# 401_GridPos4.net
KiCad netlist of a schematic drawn in Altium Designer
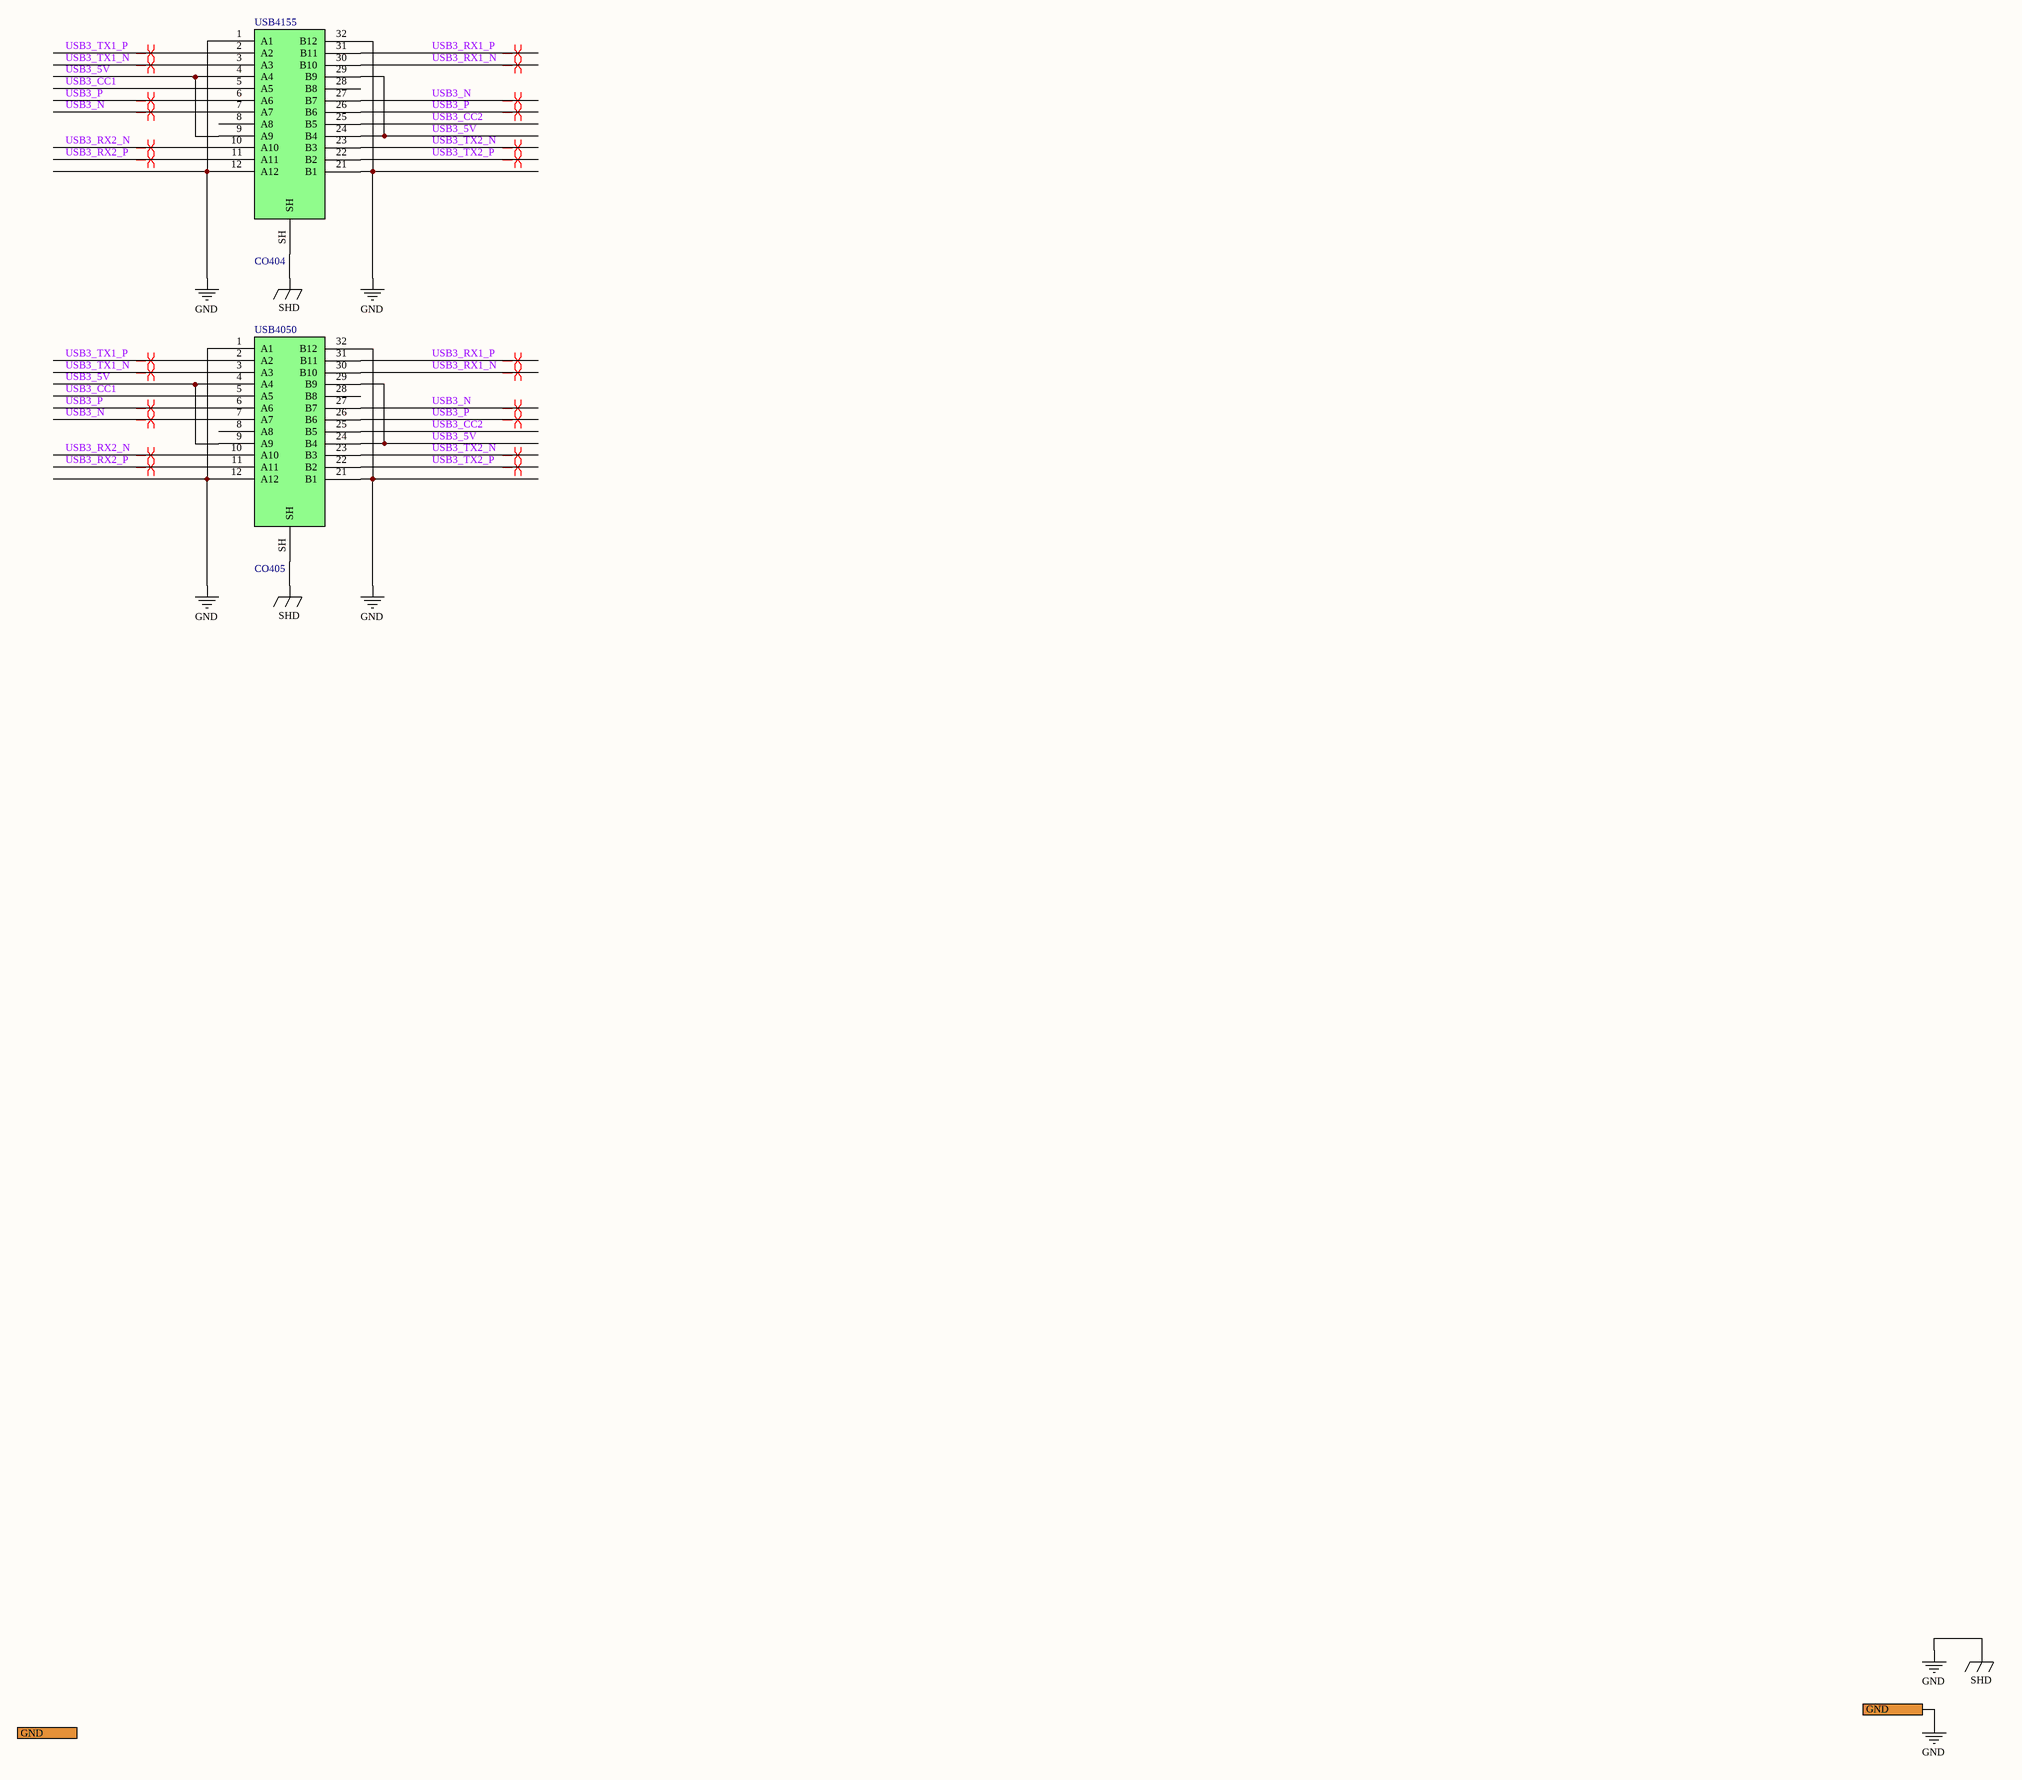
[diagram p0: 401_GridPos4.SchDoc]

(export (version "E")
  (design (tool "Eeschema 10.0.6"))
  (components
    (comp (ref "CO404")
      (value "USB4155")
      (footprint "USB4155-03-C")
      (description "USB C connector Plug Horizontal")
      (fields
        (field (name "REFVAL") "USB4155")
        (field (name "PART NUMBER") "CO0031")
        (field (name "MANFACTPART") "USB4155-03-C")
      )
      (libsource (lib "GTS_Database") (part "USB-CC"))
    )
    (comp (ref "CO405")
      (value "USB4050")
      (footprint "USB4050-30-A")
      (description "USB C connector Receptacle Horizontal")
      (fields
        (field (name "REFVAL") "USB4050")
        (field (name "PART NUMBER") "CO0039")
        (field (name "MANFACTPART") "USB4050-30-A")
      )
      (libsource (lib "GTS_Database") (part "USB-CC"))
    )
  )
  (nets
    (net (code "1") (name "/USB3_5V") (class "Default")
      (node (ref "CO404") (pin "24") (pinfunction "B4_24") (pintype "passive"))
      (node (ref "CO404") (pin "29") (pinfunction "B9_29") (pintype "passive"))
      (node (ref "CO404") (pin "4") (pinfunction "A4_4") (pintype "passive"))
      (node (ref "CO404") (pin "9") (pinfunction "A9_9") (pintype "passive"))
      (node (ref "CO405") (pin "24") (pinfunction "B4_24") (pintype "passive"))
      (node (ref "CO405") (pin "29") (pinfunction "B9_29") (pintype "passive"))
      (node (ref "CO405") (pin "4") (pinfunction "A4_4") (pintype "passive"))
      (node (ref "CO405") (pin "9") (pinfunction "A9_9") (pintype "passive"))
    )
    (net (code "2") (name "/USB3_CC1") (class "Default")
      (node (ref "CO404") (pin "5") (pinfunction "A5_5") (pintype "passive"))
      (node (ref "CO405") (pin "5") (pinfunction "A5_5") (pintype "passive"))
    )
    (net (code "3") (name "/USB3_CC2") (class "Default")
      (node (ref "CO404") (pin "25") (pinfunction "B5_25") (pintype "passive"))
      (node (ref "CO405") (pin "25") (pinfunction "B5_25") (pintype "passive"))
    )
    (net (code "4") (name "/USB3_N") (class "Default")
      (node (ref "CO404") (pin "27") (pinfunction "B7_27") (pintype "passive"))
      (node (ref "CO404") (pin "7") (pinfunction "A7_7") (pintype "passive"))
      (node (ref "CO405") (pin "27") (pinfunction "B7_27") (pintype "passive"))
      (node (ref "CO405") (pin "7") (pinfunction "A7_7") (pintype "passive"))
    )
    (net (code "5") (name "/USB3_P") (class "Default")
      (node (ref "CO404") (pin "26") (pinfunction "B6_26") (pintype "passive"))
      (node (ref "CO404") (pin "6") (pinfunction "A6_6") (pintype "passive"))
      (node (ref "CO405") (pin "26") (pinfunction "B6_26") (pintype "passive"))
      (node (ref "CO405") (pin "6") (pinfunction "A6_6") (pintype "passive"))
    )
    (net (code "6") (name "/USB3_RX1_N") (class "Default")
      (node (ref "CO404") (pin "30") (pinfunction "B10_30") (pintype "passive"))
      (node (ref "CO405") (pin "30") (pinfunction "B10_30") (pintype "passive"))
    )
    (net (code "7") (name "/USB3_RX1_P") (class "Default")
      (node (ref "CO404") (pin "31") (pinfunction "B11_31") (pintype "passive"))
      (node (ref "CO405") (pin "31") (pinfunction "B11_31") (pintype "passive"))
    )
    (net (code "8") (name "/USB3_RX2_N") (class "Default")
      (node (ref "CO404") (pin "10") (pinfunction "A10_10") (pintype "passive"))
      (node (ref "CO405") (pin "10") (pinfunction "A10_10") (pintype "passive"))
    )
    (net (code "9") (name "/USB3_RX2_P") (class "Default")
      (node (ref "CO404") (pin "11") (pinfunction "A11_11") (pintype "passive"))
      (node (ref "CO405") (pin "11") (pinfunction "A11_11") (pintype "passive"))
    )
    (net (code "10") (name "/USB3_TX1_N") (class "Default")
      (node (ref "CO404") (pin "3") (pinfunction "A3_3") (pintype "passive"))
      (node (ref "CO405") (pin "3") (pinfunction "A3_3") (pintype "passive"))
    )
    (net (code "11") (name "/USB3_TX1_P") (class "Default")
      (node (ref "CO404") (pin "2") (pinfunction "A2_2") (pintype "passive"))
      (node (ref "CO405") (pin "2") (pinfunction "A2_2") (pintype "passive"))
    )
    (net (code "12") (name "/USB3_TX2_N") (class "Default")
      (node (ref "CO404") (pin "23") (pinfunction "B3_23") (pintype "passive"))
      (node (ref "CO405") (pin "23") (pinfunction "B3_23") (pintype "passive"))
    )
    (net (code "13") (name "/USB3_TX2_P") (class "Default")
      (node (ref "CO404") (pin "22") (pinfunction "B2_22") (pintype "passive"))
      (node (ref "CO405") (pin "22") (pinfunction "B2_22") (pintype "passive"))
    )
    (net (code "14") (name "GND") (class "Default")
      (node (ref "CO404") (pin "1") (pinfunction "A1_1") (pintype "passive"))
      (node (ref "CO404") (pin "12") (pinfunction "A12_12") (pintype "passive"))
      (node (ref "CO404") (pin "21") (pinfunction "B1_21") (pintype "passive"))
      (node (ref "CO404") (pin "32") (pinfunction "B12_32") (pintype "passive"))
      (node (ref "CO404") (pin "SH") (pinfunction "SH_SH") (pintype "power_in"))
      (node (ref "CO405") (pin "1") (pinfunction "A1_1") (pintype "passive"))
      (node (ref "CO405") (pin "12") (pinfunction "A12_12") (pintype "passive"))
      (node (ref "CO405") (pin "21") (pinfunction "B1_21") (pintype "passive"))
      (node (ref "CO405") (pin "32") (pinfunction "B12_32") (pintype "passive"))
      (node (ref "CO405") (pin "SH") (pinfunction "SH_SH") (pintype "power_in"))
    )
    (net (code "15") (name "unconnected-(CO404-A8-Pad8)") (class "Default")
      (node (ref "CO404") (pin "8") (pinfunction "A8_8") (pintype "passive"))
    )
    (net (code "16") (name "unconnected-(CO404-B8-Pad28)") (class "Default")
      (node (ref "CO404") (pin "28") (pinfunction "B8_28") (pintype "passive"))
    )
    (net (code "17") (name "unconnected-(CO405-A8-Pad8)") (class "Default")
      (node (ref "CO405") (pin "8") (pinfunction "A8_8") (pintype "passive"))
    )
    (net (code "18") (name "unconnected-(CO405-B8-Pad28)") (class "Default")
      (node (ref "CO405") (pin "28") (pinfunction "B8_28") (pintype "passive"))
    )
  )
)
